# 2layer_50.net
KiCad netlist of a schematic drawn in EAGLE
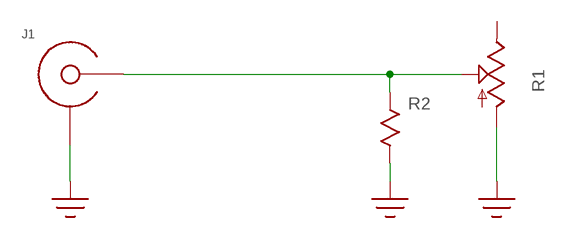
[diagram p0: schematic, sheet 1]

(export (version "E")
  (design (tool "Eeschema 10.0.6"))
  (components
    (comp (ref "J1")
      (value "EDGE_LAUNCH_JACKNARROW")
      (footprint "eagle-import:EDGE_LAUNCH_RF_CON_NARROW")
      (libsource (lib "eagle-import") (part "EDGE_LAUNCH_JACKNARROW"))
    )
    (comp (ref "R1")
      (value "TRIM_US-SP19L")
      (footprint "eagle-import:SP19L")
      (libsource (lib "eagle-import") (part "TRIM_US-SP19L"))
    )
    (comp (ref "R2")
      (value "R0603")
      (footprint "eagle-import:R0603")
      (libsource (lib "eagle-import") (part "R0603"))
    )
  )
  (nets
    (net (code "1") (name "GND") (class "Default")
      (node (ref "J1") (pin "GND@1") (pinfunction "SHIELD_GND@1") (pintype "bidirectional"))
      (node (ref "J1") (pin "GND@2") (pinfunction "SHIELD_GND@2") (pintype "bidirectional"))
      (node (ref "J1") (pin "GND@3") (pinfunction "SHIELD_GND@3") (pintype "bidirectional"))
      (node (ref "J1") (pin "GND@4") (pinfunction "SHIELD_GND@4") (pintype "bidirectional"))
      (node (ref "J1") (pin "GND@5") (pinfunction "SHIELD_GND@5") (pintype "bidirectional"))
      (node (ref "J1") (pin "GND@6") (pinfunction "SHIELD_GND@6") (pintype "bidirectional"))
      (node (ref "J1") (pin "SHIELD@1") (pinfunction "SHIELD_SHIELD@1") (pintype "bidirectional"))
      (node (ref "J1") (pin "SHIELD@2") (pinfunction "SHIELD_SHIELD@2") (pintype "bidirectional"))
      (node (ref "R1") (pin "A") (pinfunction "A_A") (pintype "passive"))
      (node (ref "R2") (pin "P$2") (pinfunction "P$4_P$2") (pintype "bidirectional"))
    )
    (net (code "2") (name "Net-(R2-P$3)") (class "Default")
      (node (ref "J1") (pin "CENTER") (pinfunction "CENTER_CENTER") (pintype "bidirectional"))
      (node (ref "R1") (pin "S") (pinfunction "S_S") (pintype "passive"))
      (node (ref "R2") (pin "P$1") (pinfunction "P$3_P$1") (pintype "bidirectional"))
    )
    (net (code "3") (name "unconnected-(R1-PadE)") (class "Default")
      (node (ref "R1") (pin "E") (pinfunction "E_E") (pintype "passive"))
    )
  )
)
